# DTLJ_hexIO.net
KiCad netlist of a schematic drawn in EAGLE
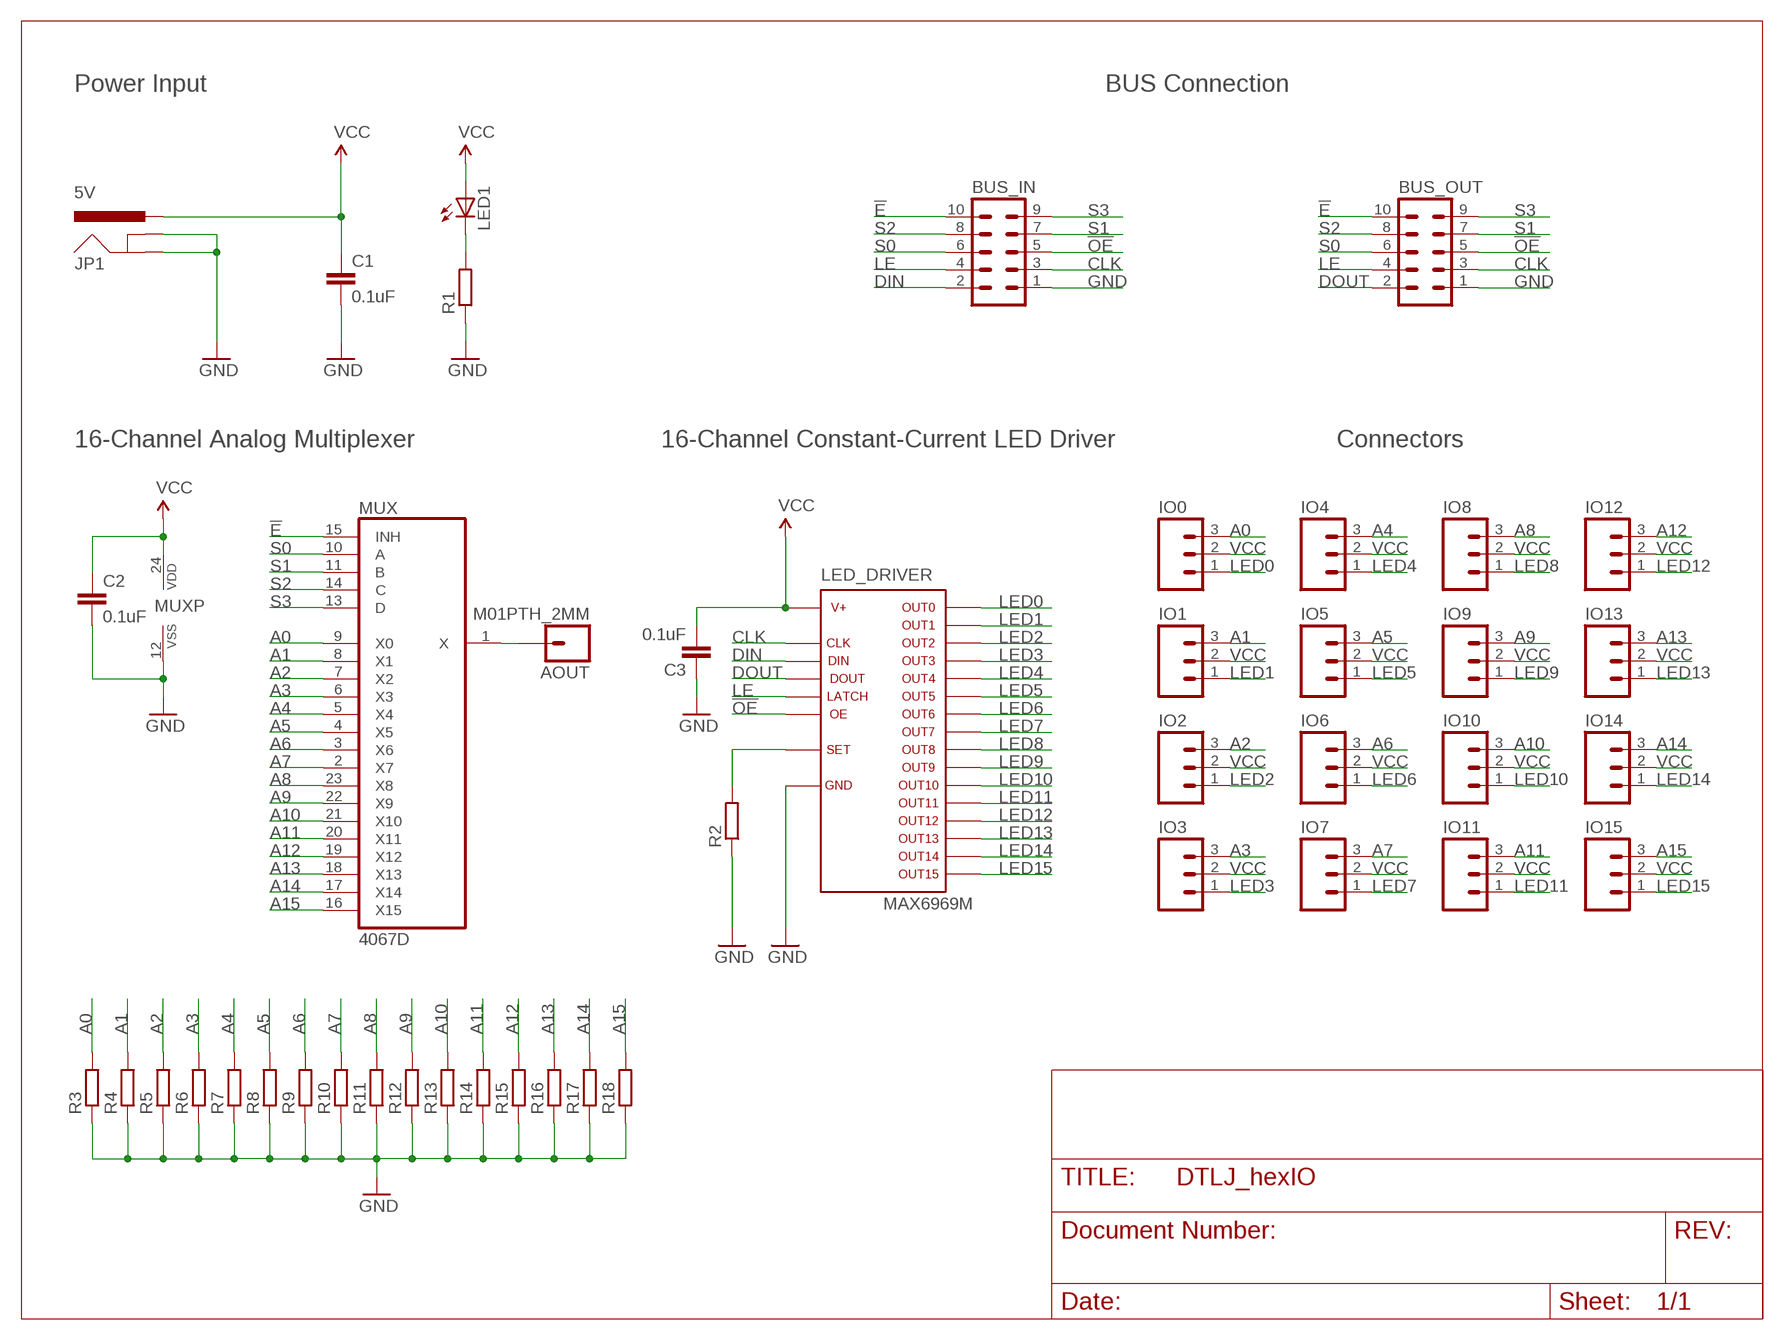
[diagram p0: schematic, sheet 1]

(export (version "E")
  (design (tool "Eeschema 10.0.6"))
  (components
    (comp (ref "AOUT")
      (value "M01PTH_2MM")
      (footprint "eagle-import:1X01_2MM")
      (libsource (lib "eagle-import") (part "M01PTH_2MM"))
    )
    (comp (ref "BUS_IN")
      (value "ML10")
      (footprint "eagle-import:ML10")
      (libsource (lib "eagle-import") (part "ML10"))
    )
    (comp (ref "BUS_OUT")
      (value "ML10")
      (footprint "eagle-import:ML10")
      (libsource (lib "eagle-import") (part "ML10"))
    )
    (comp (ref "C1")
      (value "0.1uF")
      (footprint "eagle-import:C025-024X044")
      (libsource (lib "eagle-import") (part "C-EU025-024X044"))
    )
    (comp (ref "C2")
      (value "0.1uF")
      (footprint "eagle-import:C025-024X044")
      (libsource (lib "eagle-import") (part "C-EU025-024X044"))
    )
    (comp (ref "C3")
      (value "0.1uF")
      (footprint "eagle-import:C025-024X044")
      (libsource (lib "eagle-import") (part "C-EU025-024X044"))
    )
    (comp (ref "IO0")
      (value "M03POLAR")
      (footprint "eagle-import:MOLEX-1X3")
      (libsource (lib "eagle-import") (part "M03POLAR"))
    )
    (comp (ref "IO1")
      (value "M03POLAR")
      (footprint "eagle-import:MOLEX-1X3")
      (libsource (lib "eagle-import") (part "M03POLAR"))
    )
    (comp (ref "IO2")
      (value "M03POLAR")
      (footprint "eagle-import:MOLEX-1X3")
      (libsource (lib "eagle-import") (part "M03POLAR"))
    )
    (comp (ref "IO3")
      (value "M03POLAR")
      (footprint "eagle-import:MOLEX-1X3")
      (libsource (lib "eagle-import") (part "M03POLAR"))
    )
    (comp (ref "IO4")
      (value "M03POLAR")
      (footprint "eagle-import:MOLEX-1X3")
      (libsource (lib "eagle-import") (part "M03POLAR"))
    )
    (comp (ref "IO5")
      (value "M03POLAR")
      (footprint "eagle-import:MOLEX-1X3")
      (libsource (lib "eagle-import") (part "M03POLAR"))
    )
    (comp (ref "IO6")
      (value "M03POLAR")
      (footprint "eagle-import:MOLEX-1X3")
      (libsource (lib "eagle-import") (part "M03POLAR"))
    )
    (comp (ref "IO7")
      (value "M03POLAR")
      (footprint "eagle-import:MOLEX-1X3")
      (libsource (lib "eagle-import") (part "M03POLAR"))
    )
    (comp (ref "IO8")
      (value "M03POLAR")
      (footprint "eagle-import:MOLEX-1X3")
      (libsource (lib "eagle-import") (part "M03POLAR"))
    )
    (comp (ref "IO9")
      (value "M03POLAR")
      (footprint "eagle-import:MOLEX-1X3")
      (libsource (lib "eagle-import") (part "M03POLAR"))
    )
    (comp (ref "IO10")
      (value "M03POLAR")
      (footprint "eagle-import:MOLEX-1X3")
      (libsource (lib "eagle-import") (part "M03POLAR"))
    )
    (comp (ref "IO11")
      (value "M03POLAR")
      (footprint "eagle-import:MOLEX-1X3")
      (libsource (lib "eagle-import") (part "M03POLAR"))
    )
    (comp (ref "IO12")
      (value "M03POLAR")
      (footprint "eagle-import:MOLEX-1X3")
      (libsource (lib "eagle-import") (part "M03POLAR"))
    )
    (comp (ref "IO13")
      (value "M03POLAR")
      (footprint "eagle-import:MOLEX-1X3")
      (libsource (lib "eagle-import") (part "M03POLAR"))
    )
    (comp (ref "IO14")
      (value "M03POLAR")
      (footprint "eagle-import:MOLEX-1X3")
      (libsource (lib "eagle-import") (part "M03POLAR"))
    )
    (comp (ref "IO15")
      (value "M03POLAR")
      (footprint "eagle-import:MOLEX-1X3")
      (libsource (lib "eagle-import") (part "M03POLAR"))
    )
    (comp (ref "JP1")
      (value "5V")
      (footprint "eagle-import:POWER_JACK_PTH_BREAD")
      (libsource (lib "eagle-import") (part "POWER_JACKPTH_BREAD"))
    )
    (comp (ref "LED1")
      (value "LED3MM")
      (footprint "eagle-import:LED3MM")
      (libsource (lib "eagle-import") (part "LED3MM"))
    )
    (comp (ref "LED_DRIVER")
      (value "MAX6969M")
      (footprint "eagle-import:SO24W")
      (libsource (lib "eagle-import") (part "MAX6969M"))
    )
    (comp (ref "MUX")
      (value "4067D")
      (footprint "eagle-import:SO24W")
      (libsource (lib "eagle-import") (part "4067D"))
    )
    (comp (ref "R1")
      (value "R-EU_0204/7")
      (footprint "eagle-import:0204_7")
      (libsource (lib "eagle-import") (part "R-EU_0204/7"))
    )
    (comp (ref "R2")
      (value "R-EU_0204/7")
      (footprint "eagle-import:0204_7")
      (libsource (lib "eagle-import") (part "R-EU_0204/7"))
    )
    (comp (ref "R3")
      (value "R-EU_0204/7")
      (footprint "eagle-import:0204_7")
      (libsource (lib "eagle-import") (part "R-EU_0204/7"))
    )
    (comp (ref "R4")
      (value "R-EU_0204/7")
      (footprint "eagle-import:0204_7")
      (libsource (lib "eagle-import") (part "R-EU_0204/7"))
    )
    (comp (ref "R5")
      (value "R-EU_0204/7")
      (footprint "eagle-import:0204_7")
      (libsource (lib "eagle-import") (part "R-EU_0204/7"))
    )
    (comp (ref "R6")
      (value "R-EU_0204/7")
      (footprint "eagle-import:0204_7")
      (libsource (lib "eagle-import") (part "R-EU_0204/7"))
    )
    (comp (ref "R7")
      (value "R-EU_0204/7")
      (footprint "eagle-import:0204_7")
      (libsource (lib "eagle-import") (part "R-EU_0204/7"))
    )
    (comp (ref "R8")
      (value "R-EU_0204/7")
      (footprint "eagle-import:0204_7")
      (libsource (lib "eagle-import") (part "R-EU_0204/7"))
    )
    (comp (ref "R9")
      (value "R-EU_0204/7")
      (footprint "eagle-import:0204_7")
      (libsource (lib "eagle-import") (part "R-EU_0204/7"))
    )
    (comp (ref "R10")
      (value "R-EU_0204/7")
      (footprint "eagle-import:0204_7")
      (libsource (lib "eagle-import") (part "R-EU_0204/7"))
    )
    (comp (ref "R11")
      (value "R-EU_0204/7")
      (footprint "eagle-import:0204_7")
      (libsource (lib "eagle-import") (part "R-EU_0204/7"))
    )
    (comp (ref "R12")
      (value "R-EU_0204/7")
      (footprint "eagle-import:0204_7")
      (libsource (lib "eagle-import") (part "R-EU_0204/7"))
    )
    (comp (ref "R13")
      (value "R-EU_0204/7")
      (footprint "eagle-import:0204_7")
      (libsource (lib "eagle-import") (part "R-EU_0204/7"))
    )
    (comp (ref "R14")
      (value "R-EU_0204/7")
      (footprint "eagle-import:0204_7")
      (libsource (lib "eagle-import") (part "R-EU_0204/7"))
    )
    (comp (ref "R15")
      (value "R-EU_0204/7")
      (footprint "eagle-import:0204_7")
      (libsource (lib "eagle-import") (part "R-EU_0204/7"))
    )
    (comp (ref "R16")
      (value "R-EU_0204/7")
      (footprint "eagle-import:0204_7")
      (libsource (lib "eagle-import") (part "R-EU_0204/7"))
    )
    (comp (ref "R17")
      (value "R-EU_0204/7")
      (footprint "eagle-import:0204_7")
      (libsource (lib "eagle-import") (part "R-EU_0204/7"))
    )
    (comp (ref "R18")
      (value "R-EU_0204/7")
      (footprint "eagle-import:0204_7")
      (libsource (lib "eagle-import") (part "R-EU_0204/7"))
    )
  )
  (nets
    (net (code "1") (name "/A0") (class "Default")
      (node (ref "IO0") (pin "3") (pinfunction "3_3") (pintype "passive"))
      (node (ref "MUX") (pin "9") (pinfunction "X0_9") (pintype "input"))
      (node (ref "R3") (pin "2") (pinfunction "2_2") (pintype "passive"))
    )
    (net (code "2") (name "/A1") (class "Default")
      (node (ref "IO1") (pin "3") (pinfunction "3_3") (pintype "passive"))
      (node (ref "MUX") (pin "8") (pinfunction "X1_8") (pintype "input"))
      (node (ref "R4") (pin "2") (pinfunction "2_2") (pintype "passive"))
    )
    (net (code "3") (name "/A2") (class "Default")
      (node (ref "IO2") (pin "3") (pinfunction "3_3") (pintype "passive"))
      (node (ref "MUX") (pin "7") (pinfunction "X2_7") (pintype "input"))
      (node (ref "R5") (pin "2") (pinfunction "2_2") (pintype "passive"))
    )
    (net (code "4") (name "/A3") (class "Default")
      (node (ref "IO3") (pin "3") (pinfunction "3_3") (pintype "passive"))
      (node (ref "MUX") (pin "6") (pinfunction "X3_6") (pintype "input"))
      (node (ref "R6") (pin "2") (pinfunction "2_2") (pintype "passive"))
    )
    (net (code "5") (name "/A4") (class "Default")
      (node (ref "IO4") (pin "3") (pinfunction "3_3") (pintype "passive"))
      (node (ref "MUX") (pin "5") (pinfunction "X4_5") (pintype "input"))
      (node (ref "R7") (pin "2") (pinfunction "2_2") (pintype "passive"))
    )
    (net (code "6") (name "/A5") (class "Default")
      (node (ref "IO5") (pin "3") (pinfunction "3_3") (pintype "passive"))
      (node (ref "MUX") (pin "4") (pinfunction "X5_4") (pintype "input"))
      (node (ref "R8") (pin "2") (pinfunction "2_2") (pintype "passive"))
    )
    (net (code "7") (name "/A6") (class "Default")
      (node (ref "IO6") (pin "3") (pinfunction "3_3") (pintype "passive"))
      (node (ref "MUX") (pin "3") (pinfunction "X6_3") (pintype "input"))
      (node (ref "R9") (pin "2") (pinfunction "2_2") (pintype "passive"))
    )
    (net (code "8") (name "/A7") (class "Default")
      (node (ref "IO7") (pin "3") (pinfunction "3_3") (pintype "passive"))
      (node (ref "MUX") (pin "2") (pinfunction "X7_2") (pintype "input"))
      (node (ref "R10") (pin "2") (pinfunction "2_2") (pintype "passive"))
    )
    (net (code "9") (name "/A8") (class "Default")
      (node (ref "IO8") (pin "3") (pinfunction "3_3") (pintype "passive"))
      (node (ref "MUX") (pin "23") (pinfunction "X8_23") (pintype "input"))
      (node (ref "R11") (pin "2") (pinfunction "2_2") (pintype "passive"))
    )
    (net (code "10") (name "/A9") (class "Default")
      (node (ref "IO9") (pin "3") (pinfunction "3_3") (pintype "passive"))
      (node (ref "MUX") (pin "22") (pinfunction "X9_22") (pintype "input"))
      (node (ref "R12") (pin "2") (pinfunction "2_2") (pintype "passive"))
    )
    (net (code "11") (name "/A10") (class "Default")
      (node (ref "IO10") (pin "3") (pinfunction "3_3") (pintype "passive"))
      (node (ref "MUX") (pin "21") (pinfunction "X10_21") (pintype "input"))
      (node (ref "R13") (pin "2") (pinfunction "2_2") (pintype "passive"))
    )
    (net (code "12") (name "/A11") (class "Default")
      (node (ref "IO11") (pin "3") (pinfunction "3_3") (pintype "passive"))
      (node (ref "MUX") (pin "20") (pinfunction "X11_20") (pintype "input"))
      (node (ref "R14") (pin "2") (pinfunction "2_2") (pintype "passive"))
    )
    (net (code "13") (name "/A12") (class "Default")
      (node (ref "IO12") (pin "3") (pinfunction "3_3") (pintype "passive"))
      (node (ref "MUX") (pin "19") (pinfunction "X12_19") (pintype "input"))
      (node (ref "R15") (pin "2") (pinfunction "2_2") (pintype "passive"))
    )
    (net (code "14") (name "/A13") (class "Default")
      (node (ref "IO13") (pin "3") (pinfunction "3_3") (pintype "passive"))
      (node (ref "MUX") (pin "18") (pinfunction "X13_18") (pintype "input"))
      (node (ref "R16") (pin "2") (pinfunction "2_2") (pintype "passive"))
    )
    (net (code "15") (name "/A14") (class "Default")
      (node (ref "IO14") (pin "3") (pinfunction "3_3") (pintype "passive"))
      (node (ref "MUX") (pin "17") (pinfunction "X14_17") (pintype "input"))
      (node (ref "R17") (pin "2") (pinfunction "2_2") (pintype "passive"))
    )
    (net (code "16") (name "/A15") (class "Default")
      (node (ref "IO15") (pin "3") (pinfunction "3_3") (pintype "passive"))
      (node (ref "MUX") (pin "16") (pinfunction "X15_16") (pintype "input"))
      (node (ref "R18") (pin "2") (pinfunction "2_2") (pintype "passive"))
    )
    (net (code "17") (name "/CLK") (class "Default")
      (node (ref "BUS_IN") (pin "3") (pinfunction "3_3") (pintype "passive"))
      (node (ref "BUS_OUT") (pin "3") (pinfunction "3_3") (pintype "passive"))
      (node (ref "LED_DRIVER") (pin "3") (pinfunction "P$3_3") (pintype "input"))
    )
    (net (code "18") (name "/DIN") (class "Default")
      (node (ref "BUS_IN") (pin "2") (pinfunction "2_2") (pintype "passive"))
      (node (ref "LED_DRIVER") (pin "2") (pinfunction "P$2_2") (pintype "input"))
    )
    (net (code "19") (name "/DOUT") (class "Default")
      (node (ref "BUS_OUT") (pin "2") (pinfunction "2_2") (pintype "passive"))
      (node (ref "LED_DRIVER") (pin "22") (pinfunction "P$22_22") (pintype "output"))
    )
    (net (code "20") (name "/LE") (class "Default")
      (node (ref "BUS_IN") (pin "4") (pinfunction "4_4") (pintype "passive"))
      (node (ref "BUS_OUT") (pin "4") (pinfunction "4_4") (pintype "passive"))
      (node (ref "LED_DRIVER") (pin "4") (pinfunction "P$4_4") (pintype "input"))
    )
    (net (code "21") (name "/LED0") (class "Default")
      (node (ref "IO0") (pin "1") (pinfunction "1_1") (pintype "passive"))
      (node (ref "LED_DRIVER") (pin "5") (pinfunction "P$5_5") (pintype "output"))
    )
    (net (code "22") (name "/LED1") (class "Default")
      (node (ref "IO1") (pin "1") (pinfunction "1_1") (pintype "passive"))
      (node (ref "LED_DRIVER") (pin "6") (pinfunction "P$6_6") (pintype "output"))
    )
    (net (code "23") (name "/LED2") (class "Default")
      (node (ref "IO2") (pin "1") (pinfunction "1_1") (pintype "passive"))
      (node (ref "LED_DRIVER") (pin "7") (pinfunction "P$7_7") (pintype "output"))
    )
    (net (code "24") (name "/LED3") (class "Default")
      (node (ref "IO3") (pin "1") (pinfunction "1_1") (pintype "passive"))
      (node (ref "LED_DRIVER") (pin "8") (pinfunction "P$8_8") (pintype "output"))
    )
    (net (code "25") (name "/LED4") (class "Default")
      (node (ref "IO4") (pin "1") (pinfunction "1_1") (pintype "passive"))
      (node (ref "LED_DRIVER") (pin "9") (pinfunction "P$9_9") (pintype "output"))
    )
    (net (code "26") (name "/LED5") (class "Default")
      (node (ref "IO5") (pin "1") (pinfunction "1_1") (pintype "passive"))
      (node (ref "LED_DRIVER") (pin "10") (pinfunction "P$10_10") (pintype "output"))
    )
    (net (code "27") (name "/LED6") (class "Default")
      (node (ref "IO6") (pin "1") (pinfunction "1_1") (pintype "passive"))
      (node (ref "LED_DRIVER") (pin "11") (pinfunction "P$11_11") (pintype "output"))
    )
    (net (code "28") (name "/LED7") (class "Default")
      (node (ref "IO7") (pin "1") (pinfunction "1_1") (pintype "passive"))
      (node (ref "LED_DRIVER") (pin "12") (pinfunction "P$12_12") (pintype "output"))
    )
    (net (code "29") (name "/LED8") (class "Default")
      (node (ref "IO8") (pin "1") (pinfunction "1_1") (pintype "passive"))
      (node (ref "LED_DRIVER") (pin "13") (pinfunction "P$13_13") (pintype "output"))
    )
    (net (code "30") (name "/LED9") (class "Default")
      (node (ref "IO9") (pin "1") (pinfunction "1_1") (pintype "passive"))
      (node (ref "LED_DRIVER") (pin "14") (pinfunction "P$14_14") (pintype "output"))
    )
    (net (code "31") (name "/LED10") (class "Default")
      (node (ref "IO10") (pin "1") (pinfunction "1_1") (pintype "passive"))
      (node (ref "LED_DRIVER") (pin "15") (pinfunction "P$15_15") (pintype "output"))
    )
    (net (code "32") (name "/LED11") (class "Default")
      (node (ref "IO11") (pin "1") (pinfunction "1_1") (pintype "passive"))
      (node (ref "LED_DRIVER") (pin "16") (pinfunction "P$16_16") (pintype "output"))
    )
    (net (code "33") (name "/LED12") (class "Default")
      (node (ref "IO12") (pin "1") (pinfunction "1_1") (pintype "passive"))
      (node (ref "LED_DRIVER") (pin "17") (pinfunction "P$17_17") (pintype "output"))
    )
    (net (code "34") (name "/LED13") (class "Default")
      (node (ref "IO13") (pin "1") (pinfunction "1_1") (pintype "passive"))
      (node (ref "LED_DRIVER") (pin "18") (pinfunction "P$18_18") (pintype "output"))
    )
    (net (code "35") (name "/LED14") (class "Default")
      (node (ref "IO14") (pin "1") (pinfunction "1_1") (pintype "passive"))
      (node (ref "LED_DRIVER") (pin "19") (pinfunction "P$19_19") (pintype "output"))
    )
    (net (code "36") (name "/LED15") (class "Default")
      (node (ref "IO15") (pin "1") (pinfunction "1_1") (pintype "passive"))
      (node (ref "LED_DRIVER") (pin "20") (pinfunction "P$20_20") (pintype "output"))
    )
    (net (code "37") (name "/S0") (class "Default")
      (node (ref "BUS_IN") (pin "6") (pinfunction "6_6") (pintype "passive"))
      (node (ref "BUS_OUT") (pin "6") (pinfunction "6_6") (pintype "passive"))
      (node (ref "MUX") (pin "10") (pinfunction "A_10") (pintype "input"))
    )
    (net (code "38") (name "/S1") (class "Default")
      (node (ref "BUS_IN") (pin "7") (pinfunction "7_7") (pintype "passive"))
      (node (ref "BUS_OUT") (pin "7") (pinfunction "7_7") (pintype "passive"))
      (node (ref "MUX") (pin "11") (pinfunction "B_11") (pintype "input"))
    )
    (net (code "39") (name "/S2") (class "Default")
      (node (ref "BUS_IN") (pin "8") (pinfunction "8_8") (pintype "passive"))
      (node (ref "BUS_OUT") (pin "8") (pinfunction "8_8") (pintype "passive"))
      (node (ref "MUX") (pin "14") (pinfunction "C_14") (pintype "input"))
    )
    (net (code "40") (name "/S3") (class "Default")
      (node (ref "BUS_IN") (pin "9") (pinfunction "9_9") (pintype "passive"))
      (node (ref "BUS_OUT") (pin "9") (pinfunction "9_9") (pintype "passive"))
      (node (ref "MUX") (pin "13") (pinfunction "D_13") (pintype "input"))
    )
    (net (code "41") (name "/~{E}") (class "Default")
      (node (ref "BUS_IN") (pin "10") (pinfunction "10_10") (pintype "passive"))
      (node (ref "BUS_OUT") (pin "10") (pinfunction "10_10") (pintype "passive"))
      (node (ref "MUX") (pin "15") (pinfunction "INH_15") (pintype "input"))
    )
    (net (code "42") (name "/~{OE}") (class "Default")
      (node (ref "BUS_IN") (pin "5") (pinfunction "5_5") (pintype "passive"))
      (node (ref "BUS_OUT") (pin "5") (pinfunction "5_5") (pintype "passive"))
      (node (ref "LED_DRIVER") (pin "21") (pinfunction "P$21_21") (pintype "input"))
    )
    (net (code "43") (name "GND") (class "Default")
      (node (ref "BUS_IN") (pin "1") (pinfunction "1_1") (pintype "passive"))
      (node (ref "BUS_OUT") (pin "1") (pinfunction "1_1") (pintype "passive"))
      (node (ref "C1") (pin "2") (pinfunction "2_2") (pintype "passive"))
      (node (ref "C2") (pin "2") (pinfunction "2_2") (pintype "passive"))
      (node (ref "C3") (pin "1") (pinfunction "1_1") (pintype "passive"))
      (node (ref "JP1") (pin "GND") (pinfunction "GND_GND") (pintype "bidirectional"))
      (node (ref "JP1") (pin "GNDBREAK") (pinfunction "GNDBREAK_GNDBREAK") (pintype "bidirectional"))
      (node (ref "LED_DRIVER") (pin "1") (pinfunction "P$1_1") (pintype "power_in"))
      (node (ref "MUX") (pin "12") (pinfunction "VSS_12") (pintype "power_in"))
      (node (ref "R1") (pin "1") (pinfunction "1_1") (pintype "passive"))
      (node (ref "R10") (pin "1") (pinfunction "1_1") (pintype "passive"))
      (node (ref "R11") (pin "1") (pinfunction "1_1") (pintype "passive"))
      (node (ref "R12") (pin "1") (pinfunction "1_1") (pintype "passive"))
      (node (ref "R13") (pin "1") (pinfunction "1_1") (pintype "passive"))
      (node (ref "R14") (pin "1") (pinfunction "1_1") (pintype "passive"))
      (node (ref "R15") (pin "1") (pinfunction "1_1") (pintype "passive"))
      (node (ref "R16") (pin "1") (pinfunction "1_1") (pintype "passive"))
      (node (ref "R17") (pin "1") (pinfunction "1_1") (pintype "passive"))
      (node (ref "R18") (pin "1") (pinfunction "1_1") (pintype "passive"))
      (node (ref "R2") (pin "1") (pinfunction "1_1") (pintype "passive"))
      (node (ref "R3") (pin "1") (pinfunction "1_1") (pintype "passive"))
      (node (ref "R4") (pin "1") (pinfunction "1_1") (pintype "passive"))
      (node (ref "R5") (pin "1") (pinfunction "1_1") (pintype "passive"))
      (node (ref "R6") (pin "1") (pinfunction "1_1") (pintype "passive"))
      (node (ref "R7") (pin "1") (pinfunction "1_1") (pintype "passive"))
      (node (ref "R8") (pin "1") (pinfunction "1_1") (pintype "passive"))
      (node (ref "R9") (pin "1") (pinfunction "1_1") (pintype "passive"))
    )
    (net (code "44") (name "Net-(LED1-C)") (class "Default")
      (node (ref "LED1") (pin "K") (pinfunction "C_K") (pintype "passive"))
      (node (ref "R1") (pin "2") (pinfunction "2_2") (pintype "passive"))
    )
    (net (code "45") (name "Net-(LED_DRIVER-P$23)") (class "Default")
      (node (ref "LED_DRIVER") (pin "23") (pinfunction "P$23_23") (pintype "bidirectional"))
      (node (ref "R2") (pin "2") (pinfunction "2_2") (pintype "passive"))
    )
    (net (code "46") (name "Net-(MUXA-X)") (class "Default")
      (node (ref "AOUT") (pin "1") (pinfunction "1_1") (pintype "passive"))
      (node (ref "MUX") (pin "1") (pinfunction "X_1") (pintype "output"))
    )
    (net (code "47") (name "VCC") (class "Default")
      (node (ref "C1") (pin "1") (pinfunction "1_1") (pintype "passive"))
      (node (ref "C2") (pin "1") (pinfunction "1_1") (pintype "passive"))
      (node (ref "C3") (pin "2") (pinfunction "2_2") (pintype "passive"))
      (node (ref "IO0") (pin "2") (pinfunction "2_2") (pintype "passive"))
      (node (ref "IO1") (pin "2") (pinfunction "2_2") (pintype "passive"))
      (node (ref "IO10") (pin "2") (pinfunction "2_2") (pintype "passive"))
      (node (ref "IO11") (pin "2") (pinfunction "2_2") (pintype "passive"))
      (node (ref "IO12") (pin "2") (pinfunction "2_2") (pintype "passive"))
      (node (ref "IO13") (pin "2") (pinfunction "2_2") (pintype "passive"))
      (node (ref "IO14") (pin "2") (pinfunction "2_2") (pintype "passive"))
      (node (ref "IO15") (pin "2") (pinfunction "2_2") (pintype "passive"))
      (node (ref "IO2") (pin "2") (pinfunction "2_2") (pintype "passive"))
      (node (ref "IO3") (pin "2") (pinfunction "2_2") (pintype "passive"))
      (node (ref "IO4") (pin "2") (pinfunction "2_2") (pintype "passive"))
      (node (ref "IO5") (pin "2") (pinfunction "2_2") (pintype "passive"))
      (node (ref "IO6") (pin "2") (pinfunction "2_2") (pintype "passive"))
      (node (ref "IO7") (pin "2") (pinfunction "2_2") (pintype "passive"))
      (node (ref "IO8") (pin "2") (pinfunction "2_2") (pintype "passive"))
      (node (ref "IO9") (pin "2") (pinfunction "2_2") (pintype "passive"))
      (node (ref "JP1") (pin "PWR") (pinfunction "PWR_PWR") (pintype "bidirectional"))
      (node (ref "LED1") (pin "A") (pinfunction "A_A") (pintype "passive"))
      (node (ref "LED_DRIVER") (pin "24") (pinfunction "P$24_24") (pintype "power_in"))
      (node (ref "MUX") (pin "24") (pinfunction "VDD_24") (pintype "power_in"))
    )
  )
)
